# PDB.net
KiCad netlist of a schematic drawn in EAGLE
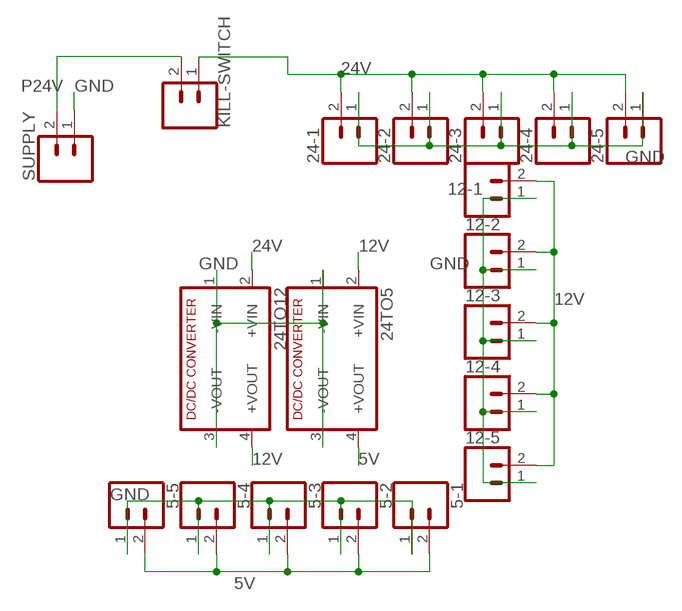
[diagram p0: schematic, sheet 1]

(export (version "E")
  (design (tool "Eeschema 10.0.6"))
  (components
    (comp (ref "5-1")
      (value "CONN_02")
      (footprint "eagle-import:1X02")
      (libsource (lib "eagle-import") (part "CONN_02"))
    )
    (comp (ref "5-2")
      (value "CONN_02")
      (footprint "eagle-import:1X02")
      (libsource (lib "eagle-import") (part "CONN_02"))
    )
    (comp (ref "5-3")
      (value "CONN_02")
      (footprint "eagle-import:1X02")
      (libsource (lib "eagle-import") (part "CONN_02"))
    )
    (comp (ref "5-4")
      (value "CONN_02")
      (footprint "eagle-import:1X02")
      (libsource (lib "eagle-import") (part "CONN_02"))
    )
    (comp (ref "5-5")
      (value "CONN_02")
      (footprint "eagle-import:1X02")
      (libsource (lib "eagle-import") (part "CONN_02"))
    )
    (comp (ref "12-1")
      (value "CONN_02")
      (footprint "eagle-import:1X02")
      (libsource (lib "eagle-import") (part "CONN_02"))
    )
    (comp (ref "12-2")
      (value "CONN_02")
      (footprint "eagle-import:1X02")
      (libsource (lib "eagle-import") (part "CONN_02"))
    )
    (comp (ref "12-3")
      (value "CONN_02")
      (footprint "eagle-import:1X02")
      (libsource (lib "eagle-import") (part "CONN_02"))
    )
    (comp (ref "12-4")
      (value "CONN_02")
      (footprint "eagle-import:1X02")
      (libsource (lib "eagle-import") (part "CONN_02"))
    )
    (comp (ref "12-5")
      (value "CONN_02")
      (footprint "eagle-import:1X02")
      (libsource (lib "eagle-import") (part "CONN_02"))
    )
    (comp (ref "24-1")
      (value "CONN_02")
      (footprint "eagle-import:1X02")
      (libsource (lib "eagle-import") (part "CONN_02"))
    )
    (comp (ref "24-2")
      (value "CONN_02")
      (footprint "eagle-import:1X02")
      (libsource (lib "eagle-import") (part "CONN_02"))
    )
    (comp (ref "24-3")
      (value "CONN_02")
      (footprint "eagle-import:1X02")
      (libsource (lib "eagle-import") (part "CONN_02"))
    )
    (comp (ref "24-4")
      (value "CONN_02")
      (footprint "eagle-import:1X02")
      (libsource (lib "eagle-import") (part "CONN_02"))
    )
    (comp (ref "24-5")
      (value "CONN_02")
      (footprint "eagle-import:1X02")
      (libsource (lib "eagle-import") (part "CONN_02"))
    )
    (comp (ref "24TO5")
      (value "NME")
      (footprint "eagle-import:NME")
      (fields (field (name "MF") "C & D TECHNOLOGIES, INC") (field (name "MPN") "NME1205D"))
      (libsource (lib "eagle-import") (part "NME"))
    )
    (comp (ref "24TO12")
      (value "NME")
      (footprint "eagle-import:NME")
      (fields (field (name "MF") "C & D TECHNOLOGIES, INC") (field (name "MPN") "NME1205D"))
      (libsource (lib "eagle-import") (part "NME"))
    )
    (comp (ref "KILL-SWITCH")
      (value "CONN_02")
      (footprint "eagle-import:1X02")
      (libsource (lib "eagle-import") (part "CONN_02"))
    )
    (comp (ref "SUPPLY")
      (value "CONN_02")
      (footprint "eagle-import:1X02")
      (libsource (lib "eagle-import") (part "CONN_02"))
    )
  )
  (nets
    (net (code "1") (name "/5V") (class "Default")
      (node (ref "24TO5") (pin "4") (pinfunction "+VOUT_4") (pintype "passive"))
      (node (ref "5-1") (pin "2") (pinfunction "2_2") (pintype "passive"))
      (node (ref "5-2") (pin "2") (pinfunction "2_2") (pintype "passive"))
      (node (ref "5-3") (pin "2") (pinfunction "2_2") (pintype "passive"))
      (node (ref "5-4") (pin "2") (pinfunction "2_2") (pintype "passive"))
      (node (ref "5-5") (pin "2") (pinfunction "2_2") (pintype "passive"))
    )
    (net (code "2") (name "/12V") (class "Default")
      (node (ref "12-1") (pin "2") (pinfunction "2_2") (pintype "passive"))
      (node (ref "12-2") (pin "2") (pinfunction "2_2") (pintype "passive"))
      (node (ref "12-3") (pin "2") (pinfunction "2_2") (pintype "passive"))
      (node (ref "12-4") (pin "2") (pinfunction "2_2") (pintype "passive"))
      (node (ref "12-5") (pin "2") (pinfunction "2_2") (pintype "passive"))
      (node (ref "24TO12") (pin "4") (pinfunction "+VOUT_4") (pintype "passive"))
      (node (ref "24TO5") (pin "2") (pinfunction "+VIN_2") (pintype "passive"))
    )
    (net (code "3") (name "/24V") (class "Default")
      (node (ref "24-1") (pin "2") (pinfunction "2_2") (pintype "passive"))
      (node (ref "24-2") (pin "2") (pinfunction "2_2") (pintype "passive"))
      (node (ref "24-3") (pin "2") (pinfunction "2_2") (pintype "passive"))
      (node (ref "24-4") (pin "2") (pinfunction "2_2") (pintype "passive"))
      (node (ref "24-5") (pin "2") (pinfunction "2_2") (pintype "passive"))
      (node (ref "24TO12") (pin "2") (pinfunction "+VIN_2") (pintype "passive"))
      (node (ref "KILL-SWITCH") (pin "1") (pinfunction "1_1") (pintype "passive"))
    )
    (net (code "4") (name "/GND") (class "Default")
      (node (ref "12-1") (pin "1") (pinfunction "1_1") (pintype "passive"))
      (node (ref "12-2") (pin "1") (pinfunction "1_1") (pintype "passive"))
      (node (ref "12-3") (pin "1") (pinfunction "1_1") (pintype "passive"))
      (node (ref "12-4") (pin "1") (pinfunction "1_1") (pintype "passive"))
      (node (ref "12-5") (pin "1") (pinfunction "1_1") (pintype "passive"))
      (node (ref "24-1") (pin "1") (pinfunction "1_1") (pintype "passive"))
      (node (ref "24-2") (pin "1") (pinfunction "1_1") (pintype "passive"))
      (node (ref "24-3") (pin "1") (pinfunction "1_1") (pintype "passive"))
      (node (ref "24-4") (pin "1") (pinfunction "1_1") (pintype "passive"))
      (node (ref "24-5") (pin "1") (pinfunction "1_1") (pintype "passive"))
      (node (ref "24TO12") (pin "1") (pinfunction "-VIN_1") (pintype "passive"))
      (node (ref "24TO12") (pin "3") (pinfunction "-VOUT_3") (pintype "passive"))
      (node (ref "24TO5") (pin "1") (pinfunction "-VIN_1") (pintype "passive"))
      (node (ref "24TO5") (pin "3") (pinfunction "-VOUT_3") (pintype "passive"))
      (node (ref "5-1") (pin "1") (pinfunction "1_1") (pintype "passive"))
      (node (ref "5-2") (pin "1") (pinfunction "1_1") (pintype "passive"))
      (node (ref "5-3") (pin "1") (pinfunction "1_1") (pintype "passive"))
      (node (ref "5-4") (pin "1") (pinfunction "1_1") (pintype "passive"))
      (node (ref "5-5") (pin "1") (pinfunction "1_1") (pintype "passive"))
      (node (ref "SUPPLY") (pin "1") (pinfunction "1_1") (pintype "passive"))
    )
    (net (code "5") (name "/P24V") (class "Default")
      (node (ref "KILL-SWITCH") (pin "2") (pinfunction "2_2") (pintype "passive"))
      (node (ref "SUPPLY") (pin "2") (pinfunction "2_2") (pintype "passive"))
    )
  )
)
